# RS485_SPI_Recieve.net
KiCad netlist of a schematic drawn in Altium Designer
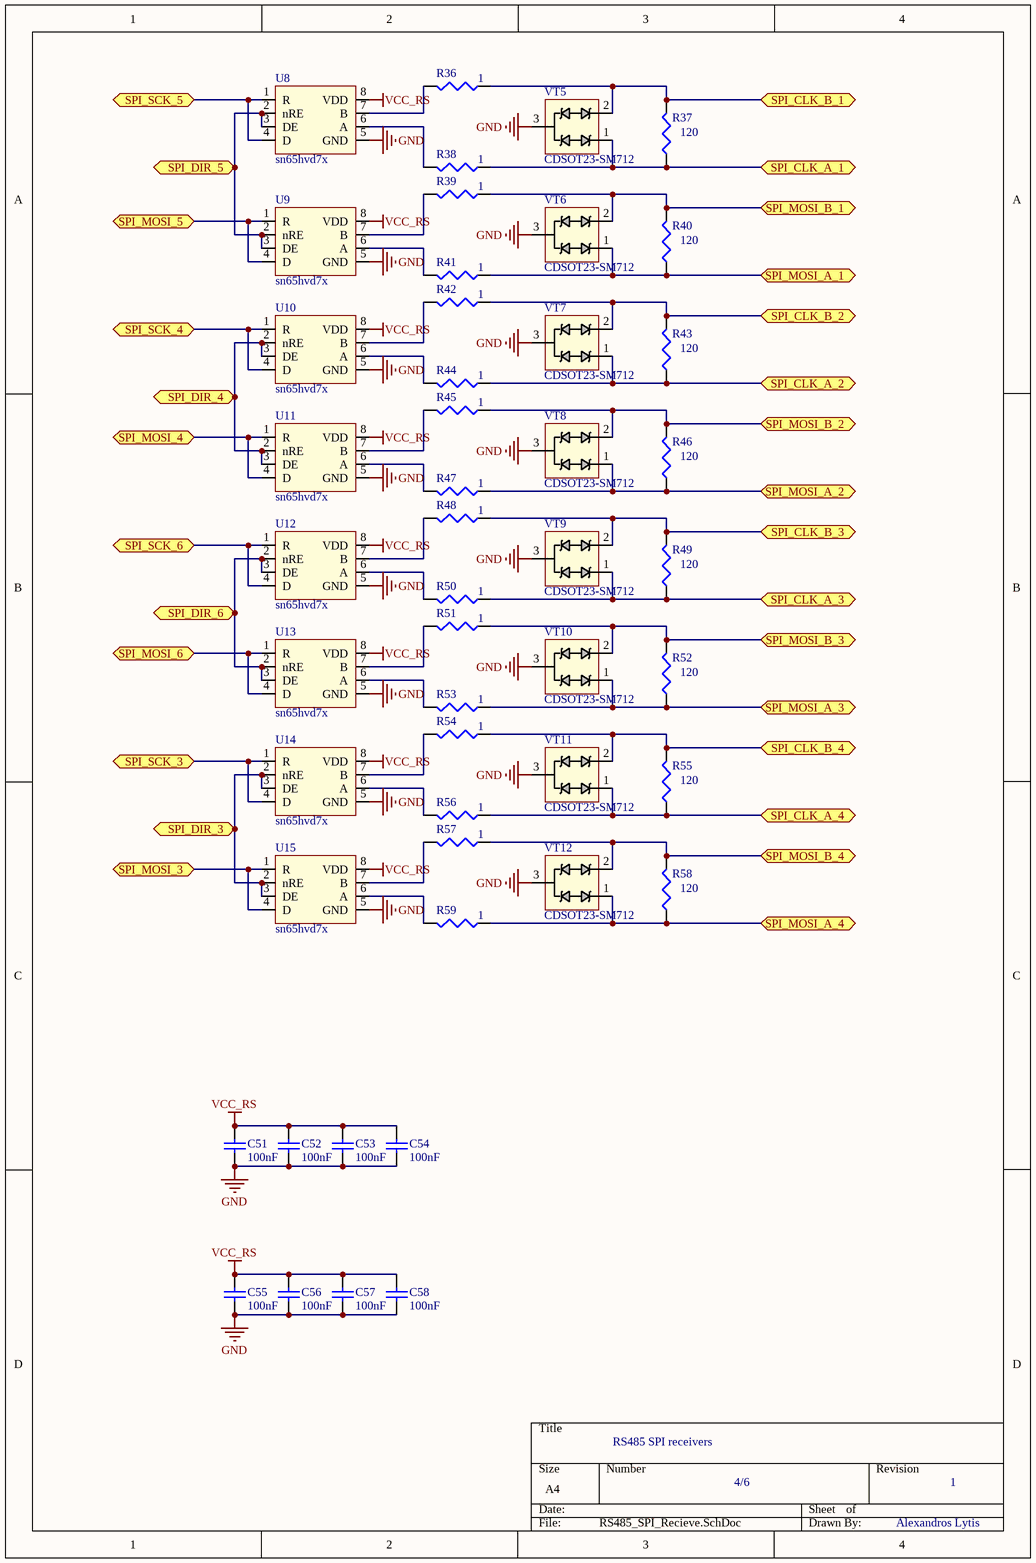
[diagram p0: RS485_SPI_Recieve.SchDoc]

(export (version "E")
  (design (tool "Eeschema 10.0.6"))
  (components
    (comp (ref "C51")
      (value "100nF")
      (footprint "CAP0603")
      (description "Capacitor (Semiconductor SIM Model)")
      (fields (field (name "Comment") "Cap Semi") (field (name "PUBLISHER") "Altium Limited"))
      (libsource (lib "Miscellaneous Devices") (part "Cap Semi"))
    )
    (comp (ref "C52")
      (value "100nF")
      (footprint "CAP0603")
      (description "Capacitor (Semiconductor SIM Model)")
      (fields (field (name "Comment") "Cap Semi") (field (name "PUBLISHER") "Altium Limited"))
      (libsource (lib "Miscellaneous Devices") (part "Cap Semi"))
    )
    (comp (ref "C53")
      (value "100nF")
      (footprint "CAP0603")
      (description "Capacitor (Semiconductor SIM Model)")
      (fields (field (name "Comment") "Cap Semi") (field (name "PUBLISHER") "Altium Limited"))
      (libsource (lib "Miscellaneous Devices") (part "Cap Semi"))
    )
    (comp (ref "C54")
      (value "100nF")
      (footprint "CAP0603")
      (description "Capacitor (Semiconductor SIM Model)")
      (fields (field (name "Comment") "Cap Semi") (field (name "PUBLISHER") "Altium Limited"))
      (libsource (lib "Miscellaneous Devices") (part "Cap Semi"))
    )
    (comp (ref "C55")
      (value "100nF")
      (footprint "CAP0603")
      (description "Capacitor (Semiconductor SIM Model)")
      (fields (field (name "Comment") "Cap Semi") (field (name "PUBLISHER") "Altium Limited"))
      (libsource (lib "Miscellaneous Devices") (part "Cap Semi"))
    )
    (comp (ref "C56")
      (value "100nF")
      (footprint "CAP0603")
      (description "Capacitor (Semiconductor SIM Model)")
      (fields (field (name "Comment") "Cap Semi") (field (name "PUBLISHER") "Altium Limited"))
      (libsource (lib "Miscellaneous Devices") (part "Cap Semi"))
    )
    (comp (ref "C57")
      (value "100nF")
      (footprint "CAP0603")
      (description "Capacitor (Semiconductor SIM Model)")
      (fields (field (name "Comment") "Cap Semi") (field (name "PUBLISHER") "Altium Limited"))
      (libsource (lib "Miscellaneous Devices") (part "Cap Semi"))
    )
    (comp (ref "C58")
      (value "100nF")
      (footprint "CAP0603")
      (description "Capacitor (Semiconductor SIM Model)")
      (fields (field (name "Comment") "Cap Semi") (field (name "PUBLISHER") "Altium Limited"))
      (libsource (lib "Miscellaneous Devices") (part "Cap Semi"))
    )
    (comp (ref "R36")
      (value "1")
      (footprint "RES0603")
      (description "Resistor")
      (fields (field (name "Comment") "p-p") (field (name "PUBLISHER") "Altium Limited"))
      (libsource (lib "Miscellaneous Devices") (part "Res3"))
    )
    (comp (ref "R37")
      (value "120")
      (footprint "RES0603")
      (description "Resistor")
      (fields (field (name "Comment") "pp") (field (name "PUBLISHER") "Altium Limited"))
      (libsource (lib "Miscellaneous Devices") (part "Res3"))
    )
    (comp (ref "R38")
      (value "1")
      (footprint "RES0603")
      (description "Resistor")
      (fields (field (name "Comment") "p-p") (field (name "PUBLISHER") "Altium Limited"))
      (libsource (lib "Miscellaneous Devices") (part "Res3"))
    )
    (comp (ref "R39")
      (value "1")
      (footprint "RES0603")
      (description "Resistor")
      (fields (field (name "Comment") "p-p") (field (name "PUBLISHER") "Altium Limited"))
      (libsource (lib "Miscellaneous Devices") (part "Res3"))
    )
    (comp (ref "R40")
      (value "120")
      (footprint "RES0603")
      (description "Resistor")
      (fields (field (name "Comment") "pp") (field (name "PUBLISHER") "Altium Limited"))
      (libsource (lib "Miscellaneous Devices") (part "Res3"))
    )
    (comp (ref "R41")
      (value "1")
      (footprint "RES0603")
      (description "Resistor")
      (fields (field (name "Comment") "p-p") (field (name "PUBLISHER") "Altium Limited"))
      (libsource (lib "Miscellaneous Devices") (part "Res3"))
    )
    (comp (ref "R42")
      (value "1")
      (footprint "RES0603")
      (description "Resistor")
      (fields (field (name "Comment") "p-p") (field (name "PUBLISHER") "Altium Limited"))
      (libsource (lib "Miscellaneous Devices") (part "Res3"))
    )
    (comp (ref "R43")
      (value "120")
      (footprint "RES0603")
      (description "Resistor")
      (fields (field (name "Comment") "pp") (field (name "PUBLISHER") "Altium Limited"))
      (libsource (lib "Miscellaneous Devices") (part "Res3"))
    )
    (comp (ref "R44")
      (value "1")
      (footprint "RES0603")
      (description "Resistor")
      (fields (field (name "Comment") "p-p") (field (name "PUBLISHER") "Altium Limited"))
      (libsource (lib "Miscellaneous Devices") (part "Res3"))
    )
    (comp (ref "R45")
      (value "1")
      (footprint "RES0603")
      (description "Resistor")
      (fields (field (name "Comment") "p-p") (field (name "PUBLISHER") "Altium Limited"))
      (libsource (lib "Miscellaneous Devices") (part "Res3"))
    )
    (comp (ref "R46")
      (value "120")
      (footprint "RES0603")
      (description "Resistor")
      (fields (field (name "Comment") "pp") (field (name "PUBLISHER") "Altium Limited"))
      (libsource (lib "Miscellaneous Devices") (part "Res3"))
    )
    (comp (ref "R47")
      (value "1")
      (footprint "RES0603")
      (description "Resistor")
      (fields (field (name "Comment") "p-p") (field (name "PUBLISHER") "Altium Limited"))
      (libsource (lib "Miscellaneous Devices") (part "Res3"))
    )
    (comp (ref "R48")
      (value "1")
      (footprint "RES0603")
      (description "Resistor")
      (fields (field (name "Comment") "p-p") (field (name "PUBLISHER") "Altium Limited"))
      (libsource (lib "Miscellaneous Devices") (part "Res3"))
    )
    (comp (ref "R49")
      (value "120")
      (footprint "RES0603")
      (description "Resistor")
      (fields (field (name "Comment") "pp") (field (name "PUBLISHER") "Altium Limited"))
      (libsource (lib "Miscellaneous Devices") (part "Res3"))
    )
    (comp (ref "R50")
      (value "1")
      (footprint "RES0603")
      (description "Resistor")
      (fields (field (name "Comment") "p-p") (field (name "PUBLISHER") "Altium Limited"))
      (libsource (lib "Miscellaneous Devices") (part "Res3"))
    )
    (comp (ref "R51")
      (value "1")
      (footprint "RES0603")
      (description "Resistor")
      (fields (field (name "Comment") "p-p") (field (name "PUBLISHER") "Altium Limited"))
      (libsource (lib "Miscellaneous Devices") (part "Res3"))
    )
    (comp (ref "R52")
      (value "120")
      (footprint "RES0603")
      (description "Resistor")
      (fields (field (name "Comment") "pp") (field (name "PUBLISHER") "Altium Limited"))
      (libsource (lib "Miscellaneous Devices") (part "Res3"))
    )
    (comp (ref "R53")
      (value "1")
      (footprint "RES0603")
      (description "Resistor")
      (fields (field (name "Comment") "p-p") (field (name "PUBLISHER") "Altium Limited"))
      (libsource (lib "Miscellaneous Devices") (part "Res3"))
    )
    (comp (ref "R54")
      (value "1")
      (footprint "RES0603")
      (description "Resistor")
      (fields (field (name "Comment") "p-p") (field (name "PUBLISHER") "Altium Limited"))
      (libsource (lib "Miscellaneous Devices") (part "Res3"))
    )
    (comp (ref "R55")
      (value "120")
      (footprint "RES0603")
      (description "Resistor")
      (fields (field (name "Comment") "pp") (field (name "PUBLISHER") "Altium Limited"))
      (libsource (lib "Miscellaneous Devices") (part "Res3"))
    )
    (comp (ref "R56")
      (value "1")
      (footprint "RES0603")
      (description "Resistor")
      (fields (field (name "Comment") "p-p") (field (name "PUBLISHER") "Altium Limited"))
      (libsource (lib "Miscellaneous Devices") (part "Res3"))
    )
    (comp (ref "R57")
      (value "1")
      (footprint "RES0603")
      (description "Resistor")
      (fields (field (name "Comment") "p-p") (field (name "PUBLISHER") "Altium Limited"))
      (libsource (lib "Miscellaneous Devices") (part "Res3"))
    )
    (comp (ref "R58")
      (value "120")
      (footprint "RES0603")
      (description "Resistor")
      (fields (field (name "Comment") "pp") (field (name "PUBLISHER") "Altium Limited"))
      (libsource (lib "Miscellaneous Devices") (part "Res3"))
    )
    (comp (ref "R59")
      (value "1")
      (footprint "RES0603")
      (description "Resistor")
      (fields (field (name "Comment") "p-p") (field (name "PUBLISHER") "Altium Limited"))
      (libsource (lib "Miscellaneous Devices") (part "Res3"))
    )
    (comp (ref "U8")
      (value "sn65hvd7x")
      (footprint "SOP127P600-8N")
      (libsource (lib "Custom_Libraries") (part "sn65hvd7x"))
    )
    (comp (ref "U9")
      (value "sn65hvd7x")
      (footprint "SOP127P600-8N")
      (libsource (lib "Custom_Libraries") (part "sn65hvd7x"))
    )
    (comp (ref "U10")
      (value "sn65hvd7x")
      (footprint "SOP127P600-8N")
      (libsource (lib "Custom_Libraries") (part "sn65hvd7x"))
    )
    (comp (ref "U11")
      (value "sn65hvd7x")
      (footprint "SOP127P600-8N")
      (libsource (lib "Custom_Libraries") (part "sn65hvd7x"))
    )
    (comp (ref "U12")
      (value "sn65hvd7x")
      (footprint "SOP127P600-8N")
      (libsource (lib "Custom_Libraries") (part "sn65hvd7x"))
    )
    (comp (ref "U13")
      (value "sn65hvd7x")
      (footprint "SOP127P600-8N")
      (libsource (lib "Custom_Libraries") (part "sn65hvd7x"))
    )
    (comp (ref "U14")
      (value "sn65hvd7x")
      (footprint "SOP127P600-8N")
      (libsource (lib "Custom_Libraries") (part "sn65hvd7x"))
    )
    (comp (ref "U15")
      (value "sn65hvd7x")
      (footprint "SOP127P600-8N")
      (libsource (lib "Custom_Libraries") (part "sn65hvd7x"))
    )
    (comp (ref "VT5")
      (value "CDSOT23-SM712")
      (footprint "SOT190P230X117-3N")
      (libsource (lib "Custom_Libraries") (part "CDSOT23-SM712"))
    )
    (comp (ref "VT6")
      (value "CDSOT23-SM712")
      (footprint "SOT190P230X117-3N")
      (libsource (lib "Custom_Libraries") (part "CDSOT23-SM712"))
    )
    (comp (ref "VT7")
      (value "CDSOT23-SM712")
      (footprint "SOT190P230X117-3N")
      (libsource (lib "Custom_Libraries") (part "CDSOT23-SM712"))
    )
    (comp (ref "VT8")
      (value "CDSOT23-SM712")
      (footprint "SOT190P230X117-3N")
      (libsource (lib "Custom_Libraries") (part "CDSOT23-SM712"))
    )
    (comp (ref "VT9")
      (value "CDSOT23-SM712")
      (footprint "SOT190P230X117-3N")
      (libsource (lib "Custom_Libraries") (part "CDSOT23-SM712"))
    )
    (comp (ref "VT10")
      (value "CDSOT23-SM712")
      (footprint "SOT190P230X117-3N")
      (libsource (lib "Custom_Libraries") (part "CDSOT23-SM712"))
    )
    (comp (ref "VT11")
      (value "CDSOT23-SM712")
      (footprint "SOT190P230X117-3N")
      (libsource (lib "Custom_Libraries") (part "CDSOT23-SM712"))
    )
    (comp (ref "VT12")
      (value "CDSOT23-SM712")
      (footprint "SOT190P230X117-3N")
      (libsource (lib "Custom_Libraries") (part "CDSOT23-SM712"))
    )
  )
  (nets
    (net (code "1") (name "/SPI_CLK_A_1") (class "Default")
      (node (ref "R37") (pin "1") (pinfunction "1_1") (pintype "passive"))
      (node (ref "R38") (pin "1") (pinfunction "1_1") (pintype "passive"))
      (node (ref "VT5") (pin "1") (pintype "passive"))
    )
    (net (code "2") (name "/SPI_CLK_A_2") (class "Default")
      (node (ref "R43") (pin "1") (pinfunction "1_1") (pintype "passive"))
      (node (ref "R44") (pin "1") (pinfunction "1_1") (pintype "passive"))
      (node (ref "VT7") (pin "1") (pintype "passive"))
    )
    (net (code "3") (name "/SPI_CLK_A_3") (class "Default")
      (node (ref "R49") (pin "1") (pinfunction "1_1") (pintype "passive"))
      (node (ref "R50") (pin "1") (pinfunction "1_1") (pintype "passive"))
      (node (ref "VT9") (pin "1") (pintype "passive"))
    )
    (net (code "4") (name "/SPI_CLK_A_4") (class "Default")
      (node (ref "R55") (pin "1") (pinfunction "1_1") (pintype "passive"))
      (node (ref "R56") (pin "1") (pinfunction "1_1") (pintype "passive"))
      (node (ref "VT11") (pin "1") (pintype "passive"))
    )
    (net (code "5") (name "/SPI_CLK_B_1") (class "Default")
      (node (ref "R36") (pin "1") (pinfunction "1_1") (pintype "passive"))
      (node (ref "R37") (pin "2") (pinfunction "2_2") (pintype "passive"))
      (node (ref "VT5") (pin "2") (pintype "passive"))
    )
    (net (code "6") (name "/SPI_CLK_B_2") (class "Default")
      (node (ref "R42") (pin "1") (pinfunction "1_1") (pintype "passive"))
      (node (ref "R43") (pin "2") (pinfunction "2_2") (pintype "passive"))
      (node (ref "VT7") (pin "2") (pintype "passive"))
    )
    (net (code "7") (name "/SPI_CLK_B_3") (class "Default")
      (node (ref "R48") (pin "1") (pinfunction "1_1") (pintype "passive"))
      (node (ref "R49") (pin "2") (pinfunction "2_2") (pintype "passive"))
      (node (ref "VT9") (pin "2") (pintype "passive"))
    )
    (net (code "8") (name "/SPI_CLK_B_4") (class "Default")
      (node (ref "R54") (pin "1") (pinfunction "1_1") (pintype "passive"))
      (node (ref "R55") (pin "2") (pinfunction "2_2") (pintype "passive"))
      (node (ref "VT11") (pin "2") (pintype "passive"))
    )
    (net (code "9") (name "/SPI_DIR_3") (class "Default")
      (node (ref "U14") (pin "2") (pinfunction "nRE_2") (pintype "passive"))
      (node (ref "U14") (pin "3") (pinfunction "DE_3") (pintype "passive"))
      (node (ref "U15") (pin "2") (pinfunction "nRE_2") (pintype "passive"))
      (node (ref "U15") (pin "3") (pinfunction "DE_3") (pintype "passive"))
    )
    (net (code "10") (name "/SPI_DIR_4") (class "Default")
      (node (ref "U10") (pin "2") (pinfunction "nRE_2") (pintype "passive"))
      (node (ref "U10") (pin "3") (pinfunction "DE_3") (pintype "passive"))
      (node (ref "U11") (pin "2") (pinfunction "nRE_2") (pintype "passive"))
      (node (ref "U11") (pin "3") (pinfunction "DE_3") (pintype "passive"))
    )
    (net (code "11") (name "/SPI_DIR_5") (class "Default")
      (node (ref "U8") (pin "2") (pinfunction "nRE_2") (pintype "passive"))
      (node (ref "U8") (pin "3") (pinfunction "DE_3") (pintype "passive"))
      (node (ref "U9") (pin "2") (pinfunction "nRE_2") (pintype "passive"))
      (node (ref "U9") (pin "3") (pinfunction "DE_3") (pintype "passive"))
    )
    (net (code "12") (name "/SPI_DIR_6") (class "Default")
      (node (ref "U12") (pin "2") (pinfunction "nRE_2") (pintype "passive"))
      (node (ref "U12") (pin "3") (pinfunction "DE_3") (pintype "passive"))
      (node (ref "U13") (pin "2") (pinfunction "nRE_2") (pintype "passive"))
      (node (ref "U13") (pin "3") (pinfunction "DE_3") (pintype "passive"))
    )
    (net (code "13") (name "/SPI_MOSI_3") (class "Default")
      (node (ref "U15") (pin "1") (pinfunction "R_1") (pintype "passive"))
      (node (ref "U15") (pin "4") (pinfunction "D_4") (pintype "passive"))
    )
    (net (code "14") (name "/SPI_MOSI_4") (class "Default")
      (node (ref "U11") (pin "1") (pinfunction "R_1") (pintype "passive"))
      (node (ref "U11") (pin "4") (pinfunction "D_4") (pintype "passive"))
    )
    (net (code "15") (name "/SPI_MOSI_5") (class "Default")
      (node (ref "U9") (pin "1") (pinfunction "R_1") (pintype "passive"))
      (node (ref "U9") (pin "4") (pinfunction "D_4") (pintype "passive"))
    )
    (net (code "16") (name "/SPI_MOSI_6") (class "Default")
      (node (ref "U13") (pin "1") (pinfunction "R_1") (pintype "passive"))
      (node (ref "U13") (pin "4") (pinfunction "D_4") (pintype "passive"))
    )
    (net (code "17") (name "/SPI_MOSI_A_1") (class "Default")
      (node (ref "R40") (pin "1") (pinfunction "1_1") (pintype "passive"))
      (node (ref "R41") (pin "1") (pinfunction "1_1") (pintype "passive"))
      (node (ref "VT6") (pin "1") (pintype "passive"))
    )
    (net (code "18") (name "/SPI_MOSI_A_2") (class "Default")
      (node (ref "R46") (pin "1") (pinfunction "1_1") (pintype "passive"))
      (node (ref "R47") (pin "1") (pinfunction "1_1") (pintype "passive"))
      (node (ref "VT8") (pin "1") (pintype "passive"))
    )
    (net (code "19") (name "/SPI_MOSI_A_3") (class "Default")
      (node (ref "R52") (pin "1") (pinfunction "1_1") (pintype "passive"))
      (node (ref "R53") (pin "1") (pinfunction "1_1") (pintype "passive"))
      (node (ref "VT10") (pin "1") (pintype "passive"))
    )
    (net (code "20") (name "/SPI_MOSI_A_4") (class "Default")
      (node (ref "R58") (pin "1") (pinfunction "1_1") (pintype "passive"))
      (node (ref "R59") (pin "1") (pinfunction "1_1") (pintype "passive"))
      (node (ref "VT12") (pin "1") (pintype "passive"))
    )
    (net (code "21") (name "/SPI_MOSI_B_1") (class "Default")
      (node (ref "R39") (pin "1") (pinfunction "1_1") (pintype "passive"))
      (node (ref "R40") (pin "2") (pinfunction "2_2") (pintype "passive"))
      (node (ref "VT6") (pin "2") (pintype "passive"))
    )
    (net (code "22") (name "/SPI_MOSI_B_2") (class "Default")
      (node (ref "R45") (pin "1") (pinfunction "1_1") (pintype "passive"))
      (node (ref "R46") (pin "2") (pinfunction "2_2") (pintype "passive"))
      (node (ref "VT8") (pin "2") (pintype "passive"))
    )
    (net (code "23") (name "/SPI_MOSI_B_3") (class "Default")
      (node (ref "R51") (pin "1") (pinfunction "1_1") (pintype "passive"))
      (node (ref "R52") (pin "2") (pinfunction "2_2") (pintype "passive"))
      (node (ref "VT10") (pin "2") (pintype "passive"))
    )
    (net (code "24") (name "/SPI_MOSI_B_4") (class "Default")
      (node (ref "R57") (pin "1") (pinfunction "1_1") (pintype "passive"))
      (node (ref "R58") (pin "2") (pinfunction "2_2") (pintype "passive"))
      (node (ref "VT12") (pin "2") (pintype "passive"))
    )
    (net (code "25") (name "/SPI_SCK_3") (class "Default")
      (node (ref "U14") (pin "1") (pinfunction "R_1") (pintype "passive"))
      (node (ref "U14") (pin "4") (pinfunction "D_4") (pintype "passive"))
    )
    (net (code "26") (name "/SPI_SCK_4") (class "Default")
      (node (ref "U10") (pin "1") (pinfunction "R_1") (pintype "passive"))
      (node (ref "U10") (pin "4") (pinfunction "D_4") (pintype "passive"))
    )
    (net (code "27") (name "/SPI_SCK_5") (class "Default")
      (node (ref "U8") (pin "1") (pinfunction "R_1") (pintype "passive"))
      (node (ref "U8") (pin "4") (pinfunction "D_4") (pintype "passive"))
    )
    (net (code "28") (name "/SPI_SCK_6") (class "Default")
      (node (ref "U12") (pin "1") (pinfunction "R_1") (pintype "passive"))
      (node (ref "U12") (pin "4") (pinfunction "D_4") (pintype "passive"))
    )
    (net (code "29") (name "GND") (class "Default")
      (node (ref "C51") (pin "1") (pinfunction "1_1") (pintype "passive"))
      (node (ref "C52") (pin "1") (pinfunction "1_1") (pintype "passive"))
      (node (ref "C53") (pin "1") (pinfunction "1_1") (pintype "passive"))
      (node (ref "C54") (pin "1") (pinfunction "1_1") (pintype "passive"))
      (node (ref "C55") (pin "1") (pinfunction "1_1") (pintype "passive"))
      (node (ref "C56") (pin "1") (pinfunction "1_1") (pintype "passive"))
      (node (ref "C57") (pin "1") (pinfunction "1_1") (pintype "passive"))
      (node (ref "C58") (pin "1") (pinfunction "1_1") (pintype "passive"))
      (node (ref "U10") (pin "5") (pinfunction "GND_5") (pintype "passive"))
      (node (ref "U11") (pin "5") (pinfunction "GND_5") (pintype "passive"))
      (node (ref "U12") (pin "5") (pinfunction "GND_5") (pintype "passive"))
      (node (ref "U13") (pin "5") (pinfunction "GND_5") (pintype "passive"))
      (node (ref "U14") (pin "5") (pinfunction "GND_5") (pintype "passive"))
      (node (ref "U15") (pin "5") (pinfunction "GND_5") (pintype "passive"))
      (node (ref "U8") (pin "5") (pinfunction "GND_5") (pintype "passive"))
      (node (ref "U9") (pin "5") (pinfunction "GND_5") (pintype "passive"))
      (node (ref "VT10") (pin "3") (pintype "passive"))
      (node (ref "VT11") (pin "3") (pintype "passive"))
      (node (ref "VT12") (pin "3") (pintype "passive"))
      (node (ref "VT5") (pin "3") (pintype "passive"))
      (node (ref "VT6") (pin "3") (pintype "passive"))
      (node (ref "VT7") (pin "3") (pintype "passive"))
      (node (ref "VT8") (pin "3") (pintype "passive"))
      (node (ref "VT9") (pin "3") (pintype "passive"))
    )
    (net (code "30") (name "Net-(U8-A)") (class "Default")
      (node (ref "R38") (pin "2") (pinfunction "2_2") (pintype "passive"))
      (node (ref "U8") (pin "6") (pinfunction "A_6") (pintype "passive"))
    )
    (net (code "31") (name "Net-(U8-B)") (class "Default")
      (node (ref "R36") (pin "2") (pinfunction "2_2") (pintype "passive"))
      (node (ref "U8") (pin "7") (pinfunction "B_7") (pintype "passive"))
    )
    (net (code "32") (name "Net-(U9-A)") (class "Default")
      (node (ref "R41") (pin "2") (pinfunction "2_2") (pintype "passive"))
      (node (ref "U9") (pin "6") (pinfunction "A_6") (pintype "passive"))
    )
    (net (code "33") (name "Net-(U9-B)") (class "Default")
      (node (ref "R39") (pin "2") (pinfunction "2_2") (pintype "passive"))
      (node (ref "U9") (pin "7") (pinfunction "B_7") (pintype "passive"))
    )
    (net (code "34") (name "Net-(U10-A)") (class "Default")
      (node (ref "R44") (pin "2") (pinfunction "2_2") (pintype "passive"))
      (node (ref "U10") (pin "6") (pinfunction "A_6") (pintype "passive"))
    )
    (net (code "35") (name "Net-(U10-B)") (class "Default")
      (node (ref "R42") (pin "2") (pinfunction "2_2") (pintype "passive"))
      (node (ref "U10") (pin "7") (pinfunction "B_7") (pintype "passive"))
    )
    (net (code "36") (name "Net-(U11-A)") (class "Default")
      (node (ref "R47") (pin "2") (pinfunction "2_2") (pintype "passive"))
      (node (ref "U11") (pin "6") (pinfunction "A_6") (pintype "passive"))
    )
    (net (code "37") (name "Net-(U11-B)") (class "Default")
      (node (ref "R45") (pin "2") (pinfunction "2_2") (pintype "passive"))
      (node (ref "U11") (pin "7") (pinfunction "B_7") (pintype "passive"))
    )
    (net (code "38") (name "Net-(U12-A)") (class "Default")
      (node (ref "R50") (pin "2") (pinfunction "2_2") (pintype "passive"))
      (node (ref "U12") (pin "6") (pinfunction "A_6") (pintype "passive"))
    )
    (net (code "39") (name "Net-(U12-B)") (class "Default")
      (node (ref "R48") (pin "2") (pinfunction "2_2") (pintype "passive"))
      (node (ref "U12") (pin "7") (pinfunction "B_7") (pintype "passive"))
    )
    (net (code "40") (name "Net-(U13-A)") (class "Default")
      (node (ref "R53") (pin "2") (pinfunction "2_2") (pintype "passive"))
      (node (ref "U13") (pin "6") (pinfunction "A_6") (pintype "passive"))
    )
    (net (code "41") (name "Net-(U13-B)") (class "Default")
      (node (ref "R51") (pin "2") (pinfunction "2_2") (pintype "passive"))
      (node (ref "U13") (pin "7") (pinfunction "B_7") (pintype "passive"))
    )
    (net (code "42") (name "Net-(U14-A)") (class "Default")
      (node (ref "R56") (pin "2") (pinfunction "2_2") (pintype "passive"))
      (node (ref "U14") (pin "6") (pinfunction "A_6") (pintype "passive"))
    )
    (net (code "43") (name "Net-(U14-B)") (class "Default")
      (node (ref "R54") (pin "2") (pinfunction "2_2") (pintype "passive"))
      (node (ref "U14") (pin "7") (pinfunction "B_7") (pintype "passive"))
    )
    (net (code "44") (name "Net-(U15-A)") (class "Default")
      (node (ref "R59") (pin "2") (pinfunction "2_2") (pintype "passive"))
      (node (ref "U15") (pin "6") (pinfunction "A_6") (pintype "passive"))
    )
    (net (code "45") (name "Net-(U15-B)") (class "Default")
      (node (ref "R57") (pin "2") (pinfunction "2_2") (pintype "passive"))
      (node (ref "U15") (pin "7") (pinfunction "B_7") (pintype "passive"))
    )
    (net (code "46") (name "VCC_RS") (class "Default")
      (node (ref "C51") (pin "2") (pinfunction "2_2") (pintype "passive"))
      (node (ref "C52") (pin "2") (pinfunction "2_2") (pintype "passive"))
      (node (ref "C53") (pin "2") (pinfunction "2_2") (pintype "passive"))
      (node (ref "C54") (pin "2") (pinfunction "2_2") (pintype "passive"))
      (node (ref "C55") (pin "2") (pinfunction "2_2") (pintype "passive"))
      (node (ref "C56") (pin "2") (pinfunction "2_2") (pintype "passive"))
      (node (ref "C57") (pin "2") (pinfunction "2_2") (pintype "passive"))
      (node (ref "C58") (pin "2") (pinfunction "2_2") (pintype "passive"))
      (node (ref "U10") (pin "8") (pinfunction "VDD_8") (pintype "passive"))
      (node (ref "U11") (pin "8") (pinfunction "VDD_8") (pintype "passive"))
      (node (ref "U12") (pin "8") (pinfunction "VDD_8") (pintype "passive"))
      (node (ref "U13") (pin "8") (pinfunction "VDD_8") (pintype "passive"))
      (node (ref "U14") (pin "8") (pinfunction "VDD_8") (pintype "passive"))
      (node (ref "U15") (pin "8") (pinfunction "VDD_8") (pintype "passive"))
      (node (ref "U8") (pin "8") (pinfunction "VDD_8") (pintype "passive"))
      (node (ref "U9") (pin "8") (pinfunction "VDD_8") (pintype "passive"))
    )
  )
)
